# v15.net
KiCad netlist of a schematic drawn in EAGLE
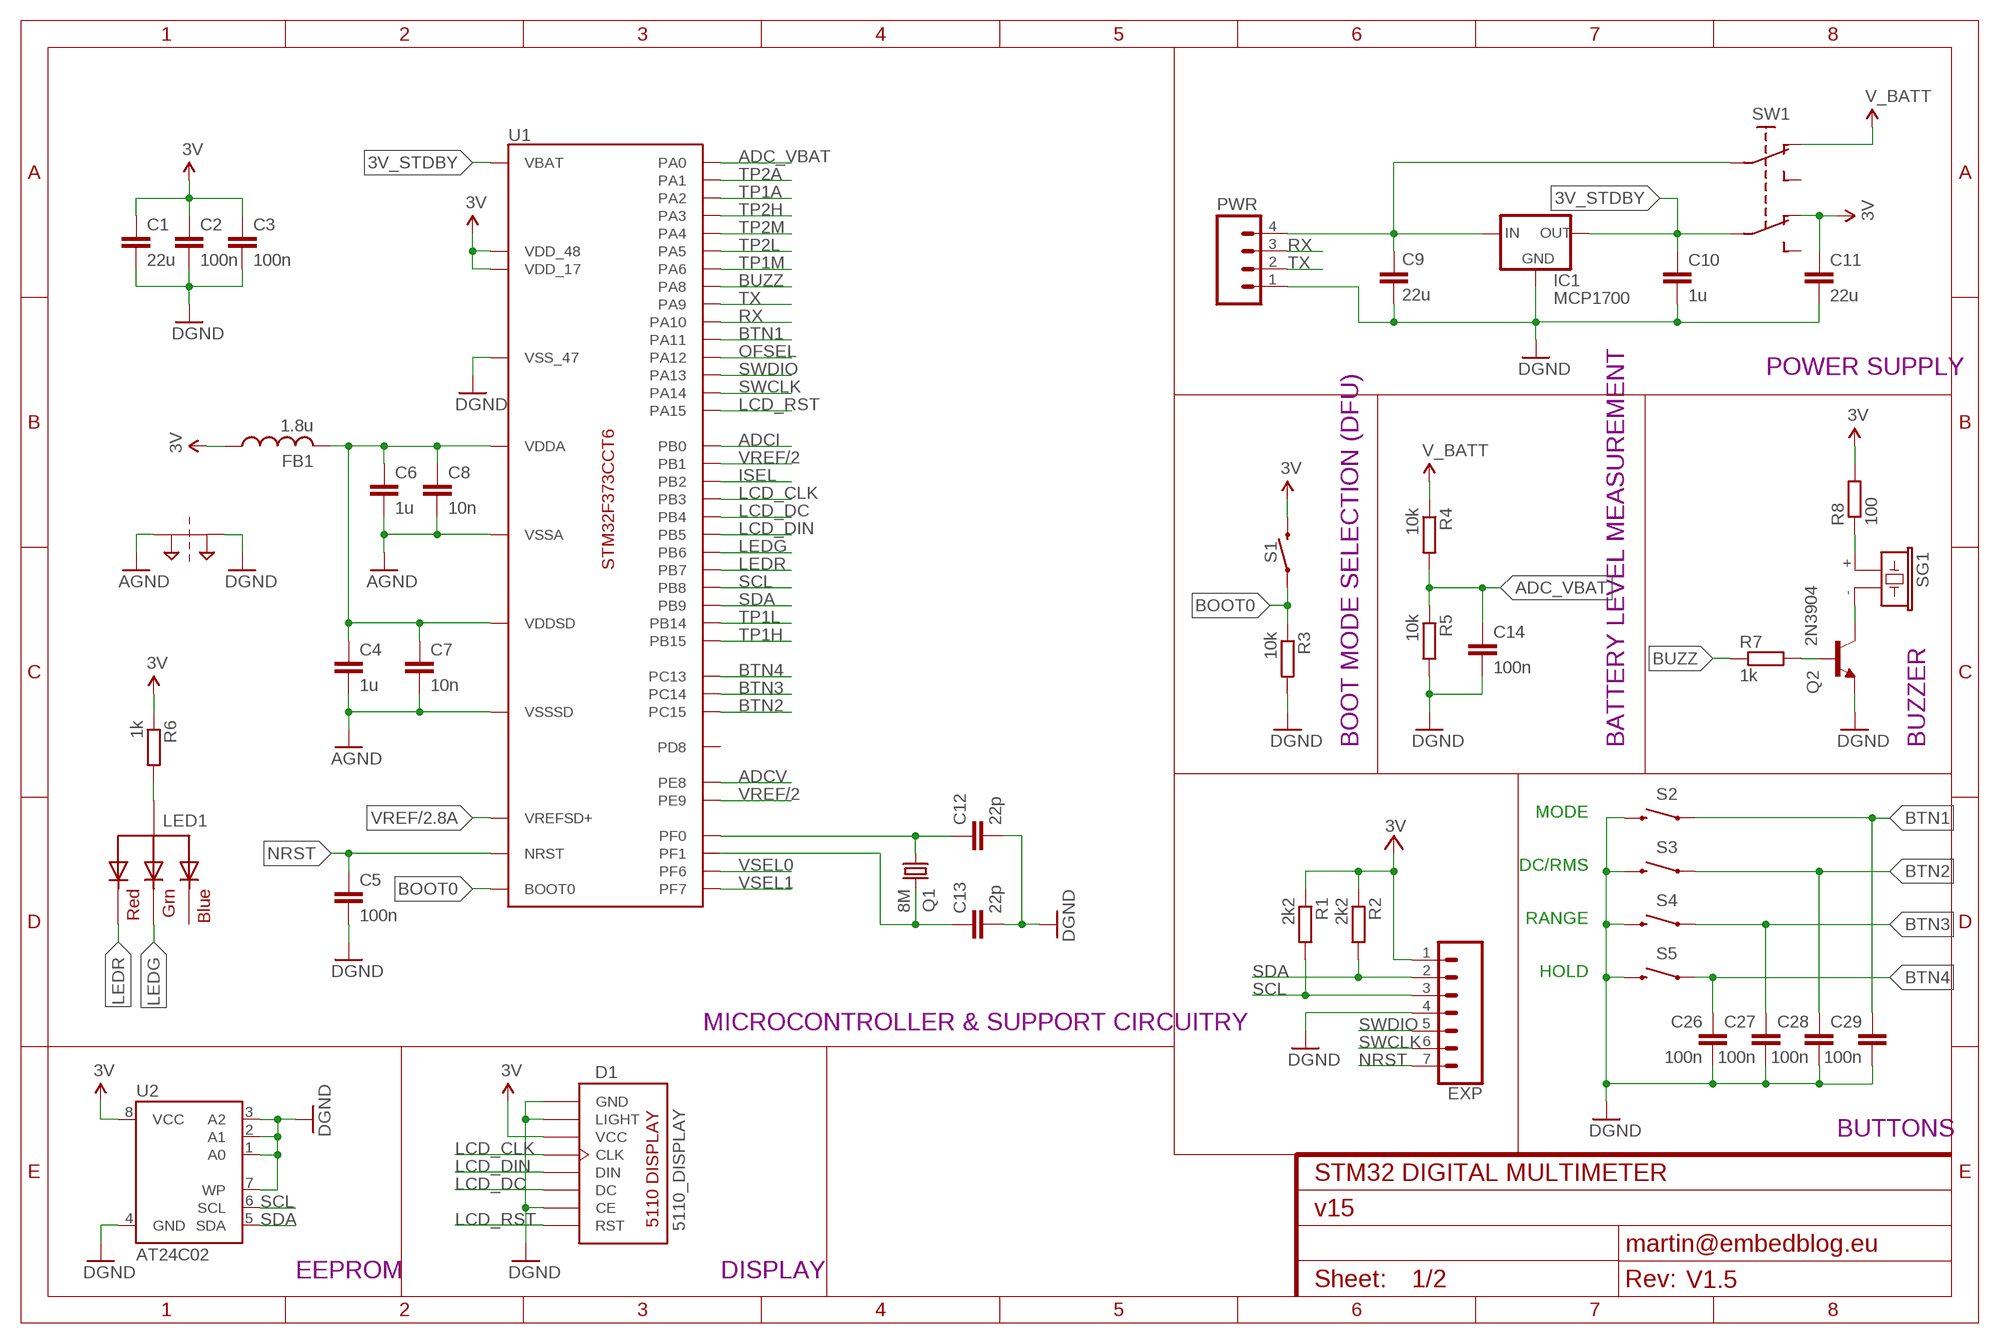
[diagram p0: schematic, sheet 1]
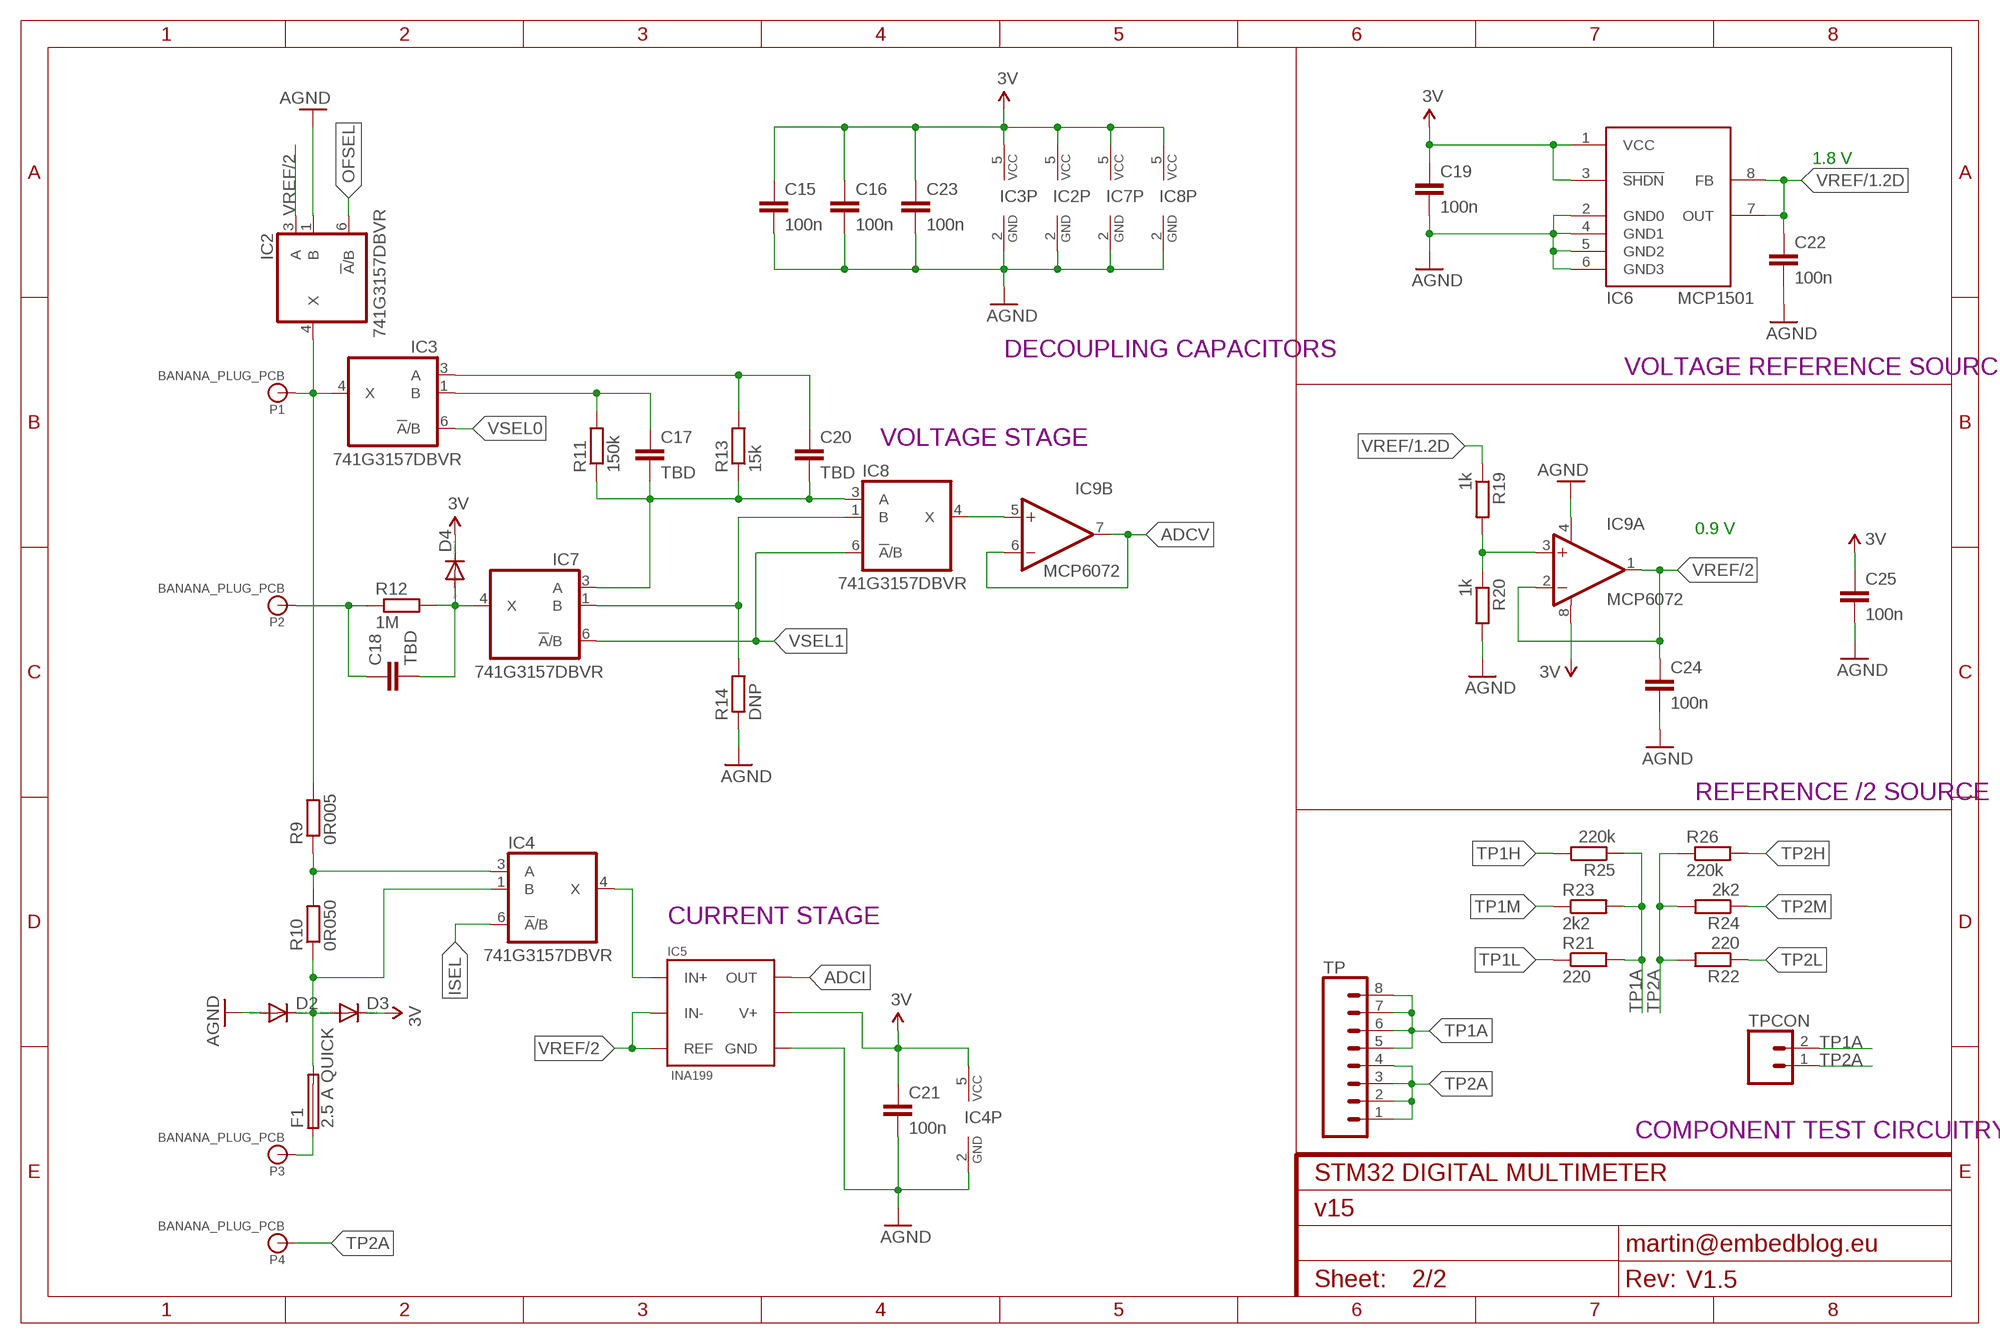
[diagram p1: schematic, sheet 2]

(export (version "E")
  (design (tool "Eeschema 10.0.6"))
  (components
    (comp (ref "C1")
      (value "22u")
      (footprint "eagle-import:C1206")
      (libsource (lib "eagle-import") (part "C-EUC1206"))
    )
    (comp (ref "C2")
      (value "100n")
      (footprint "eagle-import:C1206")
      (libsource (lib "eagle-import") (part "C-EUC1206"))
    )
    (comp (ref "C3")
      (value "100n")
      (footprint "eagle-import:C1206")
      (libsource (lib "eagle-import") (part "C-EUC1206"))
    )
    (comp (ref "C4")
      (value "1u")
      (footprint "eagle-import:C1206")
      (libsource (lib "eagle-import") (part "C-EUC1206"))
    )
    (comp (ref "C5")
      (value "100n")
      (footprint "eagle-import:C1206")
      (libsource (lib "eagle-import") (part "C-EUC1206"))
    )
    (comp (ref "C6")
      (value "1u")
      (footprint "eagle-import:C1206")
      (libsource (lib "eagle-import") (part "C-EUC1206"))
    )
    (comp (ref "C7")
      (value "10n")
      (footprint "eagle-import:C1206")
      (libsource (lib "eagle-import") (part "C-EUC1206"))
    )
    (comp (ref "C8")
      (value "10n")
      (footprint "eagle-import:C1206")
      (libsource (lib "eagle-import") (part "C-EUC1206"))
    )
    (comp (ref "C9")
      (value "22u")
      (footprint "eagle-import:C1206")
      (libsource (lib "eagle-import") (part "C-EUC1206"))
    )
    (comp (ref "C10")
      (value "1u")
      (footprint "eagle-import:C1206")
      (libsource (lib "eagle-import") (part "C-EUC1206"))
    )
    (comp (ref "C11")
      (value "22u")
      (footprint "eagle-import:C1206")
      (libsource (lib "eagle-import") (part "C-EUC1206"))
    )
    (comp (ref "C12")
      (value "22p")
      (footprint "eagle-import:C1206")
      (libsource (lib "eagle-import") (part "C-EUC1206"))
    )
    (comp (ref "C13")
      (value "22p")
      (footprint "eagle-import:C1206")
      (libsource (lib "eagle-import") (part "C-EUC1206"))
    )
    (comp (ref "C14")
      (value "100n")
      (footprint "eagle-import:C1206")
      (libsource (lib "eagle-import") (part "C-EUC1206"))
    )
    (comp (ref "C26")
      (value "100n")
      (footprint "eagle-import:C1206")
      (libsource (lib "eagle-import") (part "C-EUC1206"))
    )
    (comp (ref "C27")
      (value "100n")
      (footprint "eagle-import:C1206")
      (libsource (lib "eagle-import") (part "C-EUC1206"))
    )
    (comp (ref "C28")
      (value "100n")
      (footprint "eagle-import:C1206")
      (libsource (lib "eagle-import") (part "C-EUC1206"))
    )
    (comp (ref "C29")
      (value "100n")
      (footprint "eagle-import:C1206")
      (libsource (lib "eagle-import") (part "C-EUC1206"))
    )
    (comp (ref "D1")
      (value "5110_DISPLAY")
      (footprint "eagle-import:5110_LAYOUT")
      (libsource (lib "eagle-import") (part "5110_DISPLAY"))
    )
    (comp (ref "EXP")
      (value "CONN_07")
      (footprint "eagle-import:1X07")
      (libsource (lib "eagle-import") (part "CONN_07"))
    )
    (comp (ref "FB1")
      (value "1.8u")
      (footprint "eagle-import:1206")
      (libsource (lib "eagle-import") (part "FERRITE-BEADC"))
    )
    (comp (ref "IC1")
      (value "MCP1700")
      (footprint "eagle-import:SOT23")
      (libsource (lib "eagle-import") (part "XC63FPM"))
    )
    (comp (ref "LED1")
      (value "RGBLED_CA-5MM")
      (footprint "eagle-import:LED5MMRGB")
      (libsource (lib "eagle-import") (part "RGBLED_CA-5MM"))
    )
    (comp (ref "PT1")
      (value "2PT_GND_TIE")
      (footprint "eagle-import:2PT_GND_TIE")
      (libsource (lib "eagle-import") (part "2PT_GND_TIE"))
    )
    (comp (ref "PWR")
      (value "M04PTH")
      (footprint "eagle-import:1X04@1")
      (libsource (lib "eagle-import") (part "M04PTH"))
    )
    (comp (ref "Q1")
      (value "8M")
      (footprint "eagle-import:HC49U-V")
      (libsource (lib "eagle-import") (part "CRYSTALHC49U-V"))
    )
    (comp (ref "Q2")
      (value "2N3904")
      (footprint "eagle-import:SOT23")
      (libsource (lib "eagle-import") (part "2N3904-MMBT"))
    )
    (comp (ref "R1")
      (value "2k2")
      (footprint "eagle-import:R1206")
      (libsource (lib "eagle-import") (part "R-EU_R1206"))
    )
    (comp (ref "R2")
      (value "2k2")
      (footprint "eagle-import:R1206")
      (libsource (lib "eagle-import") (part "R-EU_R1206"))
    )
    (comp (ref "R3")
      (value "10k")
      (footprint "eagle-import:R1206")
      (libsource (lib "eagle-import") (part "R-EU_R1206"))
    )
    (comp (ref "R4")
      (value "10k")
      (footprint "eagle-import:R1206")
      (libsource (lib "eagle-import") (part "R-EU_R1206"))
    )
    (comp (ref "R5")
      (value "10k")
      (footprint "eagle-import:R1206")
      (libsource (lib "eagle-import") (part "R-EU_R1206"))
    )
    (comp (ref "R6")
      (value "1k")
      (footprint "eagle-import:R1206")
      (libsource (lib "eagle-import") (part "R-EU_R1206"))
    )
    (comp (ref "R7")
      (value "1k")
      (footprint "eagle-import:R1206")
      (libsource (lib "eagle-import") (part "R-EU_R1206"))
    )
    (comp (ref "R8")
      (value "100")
      (footprint "eagle-import:R1206")
      (libsource (lib "eagle-import") (part "R-EU_R1206"))
    )
    (comp (ref "S1")
      (value "MOMENTARY-SWITCH-SPST-PTH-6.0MM")
      (footprint "eagle-import:TACTILE_SWITCH_PTH_6.0MM")
      (libsource (lib "eagle-import") (part "MOMENTARY-SWITCH-SPST-PTH-6.0MM"))
    )
    (comp (ref "S2")
      (value "MOMENTARY-SWITCH-SPST-SMD-12MM")
      (footprint "eagle-import:TACTILE_SWITCH_SMD_12MM")
      (libsource (lib "eagle-import") (part "MOMENTARY-SWITCH-SPST-SMD-12MM"))
    )
    (comp (ref "S3")
      (value "MOMENTARY-SWITCH-SPST-SMD-12MM")
      (footprint "eagle-import:TACTILE_SWITCH_SMD_12MM")
      (libsource (lib "eagle-import") (part "MOMENTARY-SWITCH-SPST-SMD-12MM"))
    )
    (comp (ref "S4")
      (value "MOMENTARY-SWITCH-SPST-SMD-12MM")
      (footprint "eagle-import:TACTILE_SWITCH_SMD_12MM")
      (libsource (lib "eagle-import") (part "MOMENTARY-SWITCH-SPST-SMD-12MM"))
    )
    (comp (ref "S5")
      (value "MOMENTARY-SWITCH-SPST-SMD-12MM")
      (footprint "eagle-import:TACTILE_SWITCH_SMD_12MM")
      (libsource (lib "eagle-import") (part "MOMENTARY-SWITCH-SPST-SMD-12MM"))
    )
    (comp (ref "SG1")
      (value "F/CM12P")
      (footprint "eagle-import:F_CM12P")
      (libsource (lib "eagle-import") (part "F/CM12P"))
    )
    (comp (ref "SW1")
      (value "DPDT_SWITCH_SMALL")
      (footprint "eagle-import:DPDT_SMALL")
      (libsource (lib "eagle-import") (part "DPDT_SWITCH_SMALL"))
    )
    (comp (ref "U1")
      (value "STM32F373CCT6")
      (footprint "eagle-import:LQFP-48")
      (libsource (lib "eagle-import") (part "STM32F373CCT6"))
    )
    (comp (ref "U2")
      (value "AT24C02")
      (footprint "eagle-import:SOIC8")
      (libsource (lib "eagle-import") (part "24LCXX"))
    )
    (comp (ref "C15")
      (value "100n")
      (footprint "eagle-import:1206")
      (libsource (lib "eagle-import") (part "CAP1206"))
    )
    (comp (ref "C16")
      (value "100n")
      (footprint "eagle-import:1206")
      (libsource (lib "eagle-import") (part "CAP1206"))
    )
    (comp (ref "C17")
      (value "TBD")
      (footprint "eagle-import:1206")
      (libsource (lib "eagle-import") (part "CAP1206"))
    )
    (comp (ref "C18")
      (value "TBD")
      (footprint "eagle-import:1206")
      (libsource (lib "eagle-import") (part "CAP1206"))
    )
    (comp (ref "C19")
      (value "100n")
      (footprint "eagle-import:C1206")
      (libsource (lib "eagle-import") (part "C-EUC1206"))
    )
    (comp (ref "C20")
      (value "TBD")
      (footprint "eagle-import:1206")
      (libsource (lib "eagle-import") (part "CAP1206"))
    )
    (comp (ref "C21")
      (value "100n")
      (footprint "eagle-import:1206")
      (libsource (lib "eagle-import") (part "CAP1206"))
    )
    (comp (ref "C22")
      (value "100n")
      (footprint "eagle-import:C1206")
      (libsource (lib "eagle-import") (part "C-EUC1206"))
    )
    (comp (ref "C23")
      (value "100n")
      (footprint "eagle-import:1206")
      (libsource (lib "eagle-import") (part "CAP1206"))
    )
    (comp (ref "C24")
      (value "100n")
      (footprint "eagle-import:C1206")
      (libsource (lib "eagle-import") (part "C-EUC1206"))
    )
    (comp (ref "C25")
      (value "100n")
      (footprint "eagle-import:C1206")
      (libsource (lib "eagle-import") (part "C-EUC1206"))
    )
    (comp (ref "D2")
      (value "DIODE-MINIMELF")
      (footprint "eagle-import:MINIMELF")
      (libsource (lib "eagle-import") (part "DIODE-MINIMELF"))
    )
    (comp (ref "D3")
      (value "DIODE-MINIMELF")
      (footprint "eagle-import:MINIMELF")
      (libsource (lib "eagle-import") (part "DIODE-MINIMELF"))
    )
    (comp (ref "D4")
      (value "DIODE-MINIMELF")
      (footprint "eagle-import:MINIMELF")
      (libsource (lib "eagle-import") (part "DIODE-MINIMELF"))
    )
    (comp (ref "F1")
      (value "2.5 A QUICK")
      (footprint "eagle-import:SHK20L")
      (libsource (lib "eagle-import") (part "FUSESHK20L"))
    )
    (comp (ref "IC2")
      (value "741G3157DBVR")
      (footprint "eagle-import:DBV_R-PDSO-G6")
      (libsource (lib "eagle-import") (part "741G3157DBVR"))
    )
    (comp (ref "IC3")
      (value "741G3157DBVR")
      (footprint "eagle-import:DBV_R-PDSO-G6")
      (libsource (lib "eagle-import") (part "741G3157DBVR"))
    )
    (comp (ref "IC4")
      (value "741G3157DBVR")
      (footprint "eagle-import:DBV_R-PDSO-G6")
      (libsource (lib "eagle-import") (part "741G3157DBVR"))
    )
    (comp (ref "IC5")
      (value "INA199")
      (footprint "eagle-import:SC70-6")
      (libsource (lib "eagle-import") (part "INA199"))
    )
    (comp (ref "IC6")
      (value "MCP1501")
      (footprint "eagle-import:SO08")
      (libsource (lib "eagle-import") (part "MCP1501"))
    )
    (comp (ref "IC7")
      (value "741G3157DBVR")
      (footprint "eagle-import:DBV_R-PDSO-G6")
      (libsource (lib "eagle-import") (part "741G3157DBVR"))
    )
    (comp (ref "IC8")
      (value "741G3157DBVR")
      (footprint "eagle-import:DBV_R-PDSO-G6")
      (libsource (lib "eagle-import") (part "741G3157DBVR"))
    )
    (comp (ref "IC9")
      (value "MCP6072")
      (footprint "eagle-import:SO08")
      (libsource (lib "eagle-import") (part "OPAMP-DUALU"))
    )
    (comp (ref "P1")
      (value "BANANA_PLUG_PCB")
      (footprint "eagle-import:BANANA_6MMHOLE")
      (libsource (lib "eagle-import") (part "BANANA_PLUG_PCB"))
    )
    (comp (ref "P2")
      (value "BANANA_PLUG_PCB")
      (footprint "eagle-import:BANANA_6MMHOLE")
      (libsource (lib "eagle-import") (part "BANANA_PLUG_PCB"))
    )
    (comp (ref "P3")
      (value "BANANA_PLUG_PCB")
      (footprint "eagle-import:BANANA_6MMHOLE")
      (libsource (lib "eagle-import") (part "BANANA_PLUG_PCB"))
    )
    (comp (ref "P4")
      (value "BANANA_PLUG_PCB")
      (footprint "eagle-import:BANANA_6MMHOLE")
      (libsource (lib "eagle-import") (part "BANANA_PLUG_PCB"))
    )
    (comp (ref "R9")
      (value "0R005")
      (footprint "eagle-import:R1206")
      (libsource (lib "eagle-import") (part "R-EU_R1206"))
    )
    (comp (ref "R10")
      (value "0R050")
      (footprint "eagle-import:R1206")
      (libsource (lib "eagle-import") (part "R-EU_R1206"))
    )
    (comp (ref "R11")
      (value "150k")
      (footprint "eagle-import:R1206")
      (libsource (lib "eagle-import") (part "R-EU_R1206"))
    )
    (comp (ref "R12")
      (value "1M")
      (footprint "eagle-import:R1206")
      (libsource (lib "eagle-import") (part "R-EU_R1206"))
    )
    (comp (ref "R13")
      (value "15k")
      (footprint "eagle-import:R1206")
      (libsource (lib "eagle-import") (part "R-EU_R1206"))
    )
    (comp (ref "R14")
      (value "DNP")
      (footprint "eagle-import:R1206")
      (libsource (lib "eagle-import") (part "R-EU_R1206"))
    )
    (comp (ref "R19")
      (value "1k")
      (footprint "eagle-import:R1206")
      (libsource (lib "eagle-import") (part "R-EU_R1206"))
    )
    (comp (ref "R20")
      (value "1k")
      (footprint "eagle-import:R1206")
      (libsource (lib "eagle-import") (part "R-EU_R1206"))
    )
    (comp (ref "R21")
      (value "220")
      (footprint "eagle-import:R1206")
      (libsource (lib "eagle-import") (part "R-EU_R1206"))
    )
    (comp (ref "R22")
      (value "220")
      (footprint "eagle-import:R1206")
      (libsource (lib "eagle-import") (part "R-EU_R1206"))
    )
    (comp (ref "R23")
      (value "2k2")
      (footprint "eagle-import:R1206")
      (libsource (lib "eagle-import") (part "R-EU_R1206"))
    )
    (comp (ref "R24")
      (value "2k2")
      (footprint "eagle-import:R1206")
      (libsource (lib "eagle-import") (part "R-EU_R1206"))
    )
    (comp (ref "R25")
      (value "220k")
      (footprint "eagle-import:R1206")
      (libsource (lib "eagle-import") (part "R-EU_R1206"))
    )
    (comp (ref "R26")
      (value "220k")
      (footprint "eagle-import:R1206")
      (libsource (lib "eagle-import") (part "R-EU_R1206"))
    )
    (comp (ref "TP")
      (value "CONN_08SMD-STRAIGHT-FEMALE")
      (footprint "eagle-import:1X08_SMD")
      (libsource (lib "eagle-import") (part "CONN_08SMD-STRAIGHT-FEMALE"))
    )
    (comp (ref "TPCON")
      (value "CONN_02")
      (footprint "eagle-import:1X02")
      (libsource (lib "eagle-import") (part "CONN_02"))
    )
  )
  (nets
    (net (code "1") (name "3V") (class "Default")
      (node (ref "C1") (pin "1") (pinfunction "1_1") (pintype "passive"))
      (node (ref "C11") (pin "1") (pinfunction "1_1") (pintype "passive"))
      (node (ref "C15") (pin "1") (pinfunction "1_1") (pintype "passive"))
      (node (ref "C16") (pin "1") (pinfunction "1_1") (pintype "passive"))
      (node (ref "C19") (pin "1") (pinfunction "1_1") (pintype "passive"))
      (node (ref "C2") (pin "1") (pinfunction "1_1") (pintype "passive"))
      (node (ref "C21") (pin "1") (pinfunction "1_1") (pintype "passive"))
      (node (ref "C23") (pin "1") (pinfunction "1_1") (pintype "passive"))
      (node (ref "C25") (pin "1") (pinfunction "1_1") (pintype "passive"))
      (node (ref "C3") (pin "1") (pinfunction "1_1") (pintype "passive"))
      (node (ref "D1") (pin "VCC") (pinfunction "VCC_VCC") (pintype "bidirectional"))
      (node (ref "D3") (pin "C") (pinfunction "C_C") (pintype "passive"))
      (node (ref "D4") (pin "C") (pinfunction "C_C") (pintype "passive"))
      (node (ref "EXP") (pin "1") (pinfunction "1_1") (pintype "passive"))
      (node (ref "FB1") (pin "1") (pinfunction "1_1") (pintype "passive"))
      (node (ref "IC2") (pin "5") (pinfunction "VCC_5") (pintype "power_in"))
      (node (ref "IC3") (pin "5") (pinfunction "VCC_5") (pintype "power_in"))
      (node (ref "IC4") (pin "5") (pinfunction "VCC_5") (pintype "power_in"))
      (node (ref "IC5") (pin "3") (pinfunction "V+_3") (pintype "bidirectional"))
      (node (ref "IC6") (pin "1") (pinfunction "VCC_1") (pintype "bidirectional"))
      (node (ref "IC6") (pin "3") (pinfunction "~{SHDN}_3") (pintype "bidirectional"))
      (node (ref "IC7") (pin "5") (pinfunction "VCC_5") (pintype "power_in"))
      (node (ref "IC8") (pin "5") (pinfunction "VCC_5") (pintype "power_in"))
      (node (ref "IC9") (pin "8") (pinfunction "V+_8") (pintype "power_in"))
      (node (ref "R1") (pin "1") (pinfunction "1_1") (pintype "passive"))
      (node (ref "R2") (pin "1") (pinfunction "1_1") (pintype "passive"))
      (node (ref "R6") (pin "1") (pinfunction "1_1") (pintype "passive"))
      (node (ref "R8") (pin "2") (pinfunction "2_2") (pintype "passive"))
      (node (ref "S1") (pin "3") (pinfunction "2_3") (pintype "passive"))
      (node (ref "SW1") (pin "P$6") (pinfunction "NC2_P$6") (pintype "passive"))
      (node (ref "U1") (pin "17") (pinfunction "VDD_17_17") (pintype "bidirectional"))
      (node (ref "U1") (pin "48") (pinfunction "VDD_48_48") (pintype "bidirectional"))
      (node (ref "U2") (pin "8") (pinfunction "VCC_8") (pintype "power_in"))
    )
    (net (code "2") (name "3V_STDBY") (class "Default")
      (node (ref "C10") (pin "1") (pinfunction "1_1") (pintype "passive"))
      (node (ref "IC1") (pin "2") (pinfunction "OUT_2") (pintype "passive"))
      (node (ref "SW1") (pin "P$5") (pinfunction "I2_P$5") (pintype "passive"))
      (node (ref "U1") (pin "1") (pinfunction "VBAT_1") (pintype "bidirectional"))
    )
    (net (code "3") (name "ADCI") (class "Default")
      (node (ref "IC5") (pin "6") (pinfunction "OUT_6") (pintype "bidirectional"))
      (node (ref "U1") (pin "18") (pinfunction "PB0_18") (pintype "bidirectional"))
    )
    (net (code "4") (name "ADCV") (class "Default")
      (node (ref "IC9") (pin "6") (pinfunction "-IN_6") (pintype "input"))
      (node (ref "IC9") (pin "7") (pinfunction "OUT_7") (pintype "output"))
      (node (ref "U1") (pin "21") (pinfunction "PE8_21") (pintype "bidirectional"))
    )
    (net (code "5") (name "ADC_VBAT") (class "Default")
      (node (ref "C14") (pin "1") (pinfunction "1_1") (pintype "passive"))
      (node (ref "R4") (pin "2") (pinfunction "2_2") (pintype "passive"))
      (node (ref "R5") (pin "1") (pinfunction "1_1") (pintype "passive"))
      (node (ref "U1") (pin "10") (pinfunction "PA0_10") (pintype "bidirectional"))
    )
    (net (code "6") (name "AGND") (class "Default")
      (node (ref "C15") (pin "2") (pinfunction "2_2") (pintype "passive"))
      (node (ref "C16") (pin "2") (pinfunction "2_2") (pintype "passive"))
      (node (ref "C19") (pin "2") (pinfunction "2_2") (pintype "passive"))
      (node (ref "C21") (pin "2") (pinfunction "2_2") (pintype "passive"))
      (node (ref "C22") (pin "2") (pinfunction "2_2") (pintype "passive"))
      (node (ref "C23") (pin "2") (pinfunction "2_2") (pintype "passive"))
      (node (ref "C24") (pin "2") (pinfunction "2_2") (pintype "passive"))
      (node (ref "C25") (pin "2") (pinfunction "2_2") (pintype "passive"))
      (node (ref "C4") (pin "2") (pinfunction "2_2") (pintype "passive"))
      (node (ref "C6") (pin "2") (pinfunction "2_2") (pintype "passive"))
      (node (ref "C7") (pin "2") (pinfunction "2_2") (pintype "passive"))
      (node (ref "C8") (pin "2") (pinfunction "2_2") (pintype "passive"))
      (node (ref "D2") (pin "A") (pinfunction "A_A") (pintype "passive"))
      (node (ref "IC2") (pin "1") (pinfunction "B_1") (pintype "bidirectional"))
      (node (ref "IC2") (pin "2") (pinfunction "GND_2") (pintype "power_in"))
      (node (ref "IC3") (pin "2") (pinfunction "GND_2") (pintype "power_in"))
      (node (ref "IC4") (pin "2") (pinfunction "GND_2") (pintype "power_in"))
      (node (ref "IC5") (pin "2") (pinfunction "GND_2") (pintype "bidirectional"))
      (node (ref "IC6") (pin "2") (pinfunction "GND0_2") (pintype "bidirectional"))
      (node (ref "IC6") (pin "4") (pinfunction "GND1_4") (pintype "bidirectional"))
      (node (ref "IC6") (pin "5") (pinfunction "GND2_5") (pintype "bidirectional"))
      (node (ref "IC6") (pin "6") (pinfunction "GND3_6") (pintype "bidirectional"))
      (node (ref "IC7") (pin "2") (pinfunction "GND_2") (pintype "power_in"))
      (node (ref "IC8") (pin "2") (pinfunction "GND_2") (pintype "power_in"))
      (node (ref "IC9") (pin "4") (pinfunction "V-_4") (pintype "power_in"))
      (node (ref "PT1") (pin "P$1") (pinfunction "P$1_P$1") (pintype "bidirectional"))
      (node (ref "R14") (pin "1") (pinfunction "1_1") (pintype "passive"))
      (node (ref "R20") (pin "2") (pinfunction "2_2") (pintype "passive"))
      (node (ref "U1") (pin "23") (pinfunction "VSSSD_23") (pintype "bidirectional"))
      (node (ref "U1") (pin "8") (pinfunction "VSSA_8") (pintype "bidirectional"))
    )
    (net (code "7") (name "BOOT0") (class "Default")
      (node (ref "R3") (pin "1") (pinfunction "1_1") (pintype "passive"))
      (node (ref "S1") (pin "1") (pinfunction "1_1") (pintype "passive"))
      (node (ref "U1") (pin "44") (pinfunction "BOOT0_44") (pintype "bidirectional"))
    )
    (net (code "8") (name "BTN1") (class "Default")
      (node (ref "C29") (pin "1") (pinfunction "1_1") (pintype "passive"))
      (node (ref "S2") (pin "1") (pinfunction "1_1") (pintype "passive"))
      (node (ref "U1") (pin "32") (pinfunction "PA11_32") (pintype "bidirectional"))
    )
    (net (code "9") (name "BTN2") (class "Default")
      (node (ref "C28") (pin "1") (pinfunction "1_1") (pintype "passive"))
      (node (ref "S3") (pin "1") (pinfunction "1_1") (pintype "passive"))
      (node (ref "U1") (pin "4") (pinfunction "PC15_4") (pintype "bidirectional"))
    )
    (net (code "10") (name "BTN3") (class "Default")
      (node (ref "C27") (pin "1") (pinfunction "1_1") (pintype "passive"))
      (node (ref "S4") (pin "1") (pinfunction "1_1") (pintype "passive"))
      (node (ref "U1") (pin "3") (pinfunction "PC14_3") (pintype "bidirectional"))
    )
    (net (code "11") (name "BTN4") (class "Default")
      (node (ref "C26") (pin "1") (pinfunction "1_1") (pintype "passive"))
      (node (ref "S5") (pin "1") (pinfunction "1_1") (pintype "passive"))
      (node (ref "U1") (pin "2") (pinfunction "PC13_2") (pintype "bidirectional"))
    )
    (net (code "12") (name "BUZZ") (class "Default")
      (node (ref "R7") (pin "1") (pinfunction "1_1") (pintype "passive"))
      (node (ref "U1") (pin "29") (pinfunction "PA8_29") (pintype "bidirectional"))
    )
    (net (code "13") (name "GND") (class "Default")
      (node (ref "C1") (pin "2") (pinfunction "2_2") (pintype "passive"))
      (node (ref "C10") (pin "2") (pinfunction "2_2") (pintype "passive"))
      (node (ref "C11") (pin "2") (pinfunction "2_2") (pintype "passive"))
      (node (ref "C12") (pin "2") (pinfunction "2_2") (pintype "passive"))
      (node (ref "C13") (pin "2") (pinfunction "2_2") (pintype "passive"))
      (node (ref "C14") (pin "2") (pinfunction "2_2") (pintype "passive"))
      (node (ref "C2") (pin "2") (pinfunction "2_2") (pintype "passive"))
      (node (ref "C26") (pin "2") (pinfunction "2_2") (pintype "passive"))
      (node (ref "C27") (pin "2") (pinfunction "2_2") (pintype "passive"))
      (node (ref "C28") (pin "2") (pinfunction "2_2") (pintype "passive"))
      (node (ref "C29") (pin "2") (pinfunction "2_2") (pintype "passive"))
      (node (ref "C3") (pin "2") (pinfunction "2_2") (pintype "passive"))
      (node (ref "C5") (pin "2") (pinfunction "2_2") (pintype "passive"))
      (node (ref "C9") (pin "2") (pinfunction "2_2") (pintype "passive"))
      (node (ref "D1") (pin "CE") (pinfunction "CE_CE") (pintype "bidirectional"))
      (node (ref "D1") (pin "GND") (pinfunction "GND_GND") (pintype "bidirectional"))
      (node (ref "D1") (pin "LIGHT") (pinfunction "LIGHT_LIGHT") (pintype "bidirectional"))
      (node (ref "EXP") (pin "4") (pinfunction "4_4") (pintype "passive"))
      (node (ref "IC1") (pin "1") (pinfunction "GND_1") (pintype "input"))
      (node (ref "PT1") (pin "P$2") (pinfunction "P$2_P$2") (pintype "bidirectional"))
      (node (ref "PWR") (pin "1") (pinfunction "1_1") (pintype "passive"))
      (node (ref "Q2") (pin "2") (pinfunction "E_2") (pintype "passive"))
      (node (ref "R3") (pin "2") (pinfunction "2_2") (pintype "passive"))
      (node (ref "R5") (pin "2") (pinfunction "2_2") (pintype "passive"))
      (node (ref "S2") (pin "3") (pinfunction "2_3") (pintype "passive"))
      (node (ref "S3") (pin "3") (pinfunction "2_3") (pintype "passive"))
      (node (ref "S4") (pin "3") (pinfunction "2_3") (pintype "passive"))
      (node (ref "S5") (pin "3") (pinfunction "2_3") (pintype "passive"))
      (node (ref "U1") (pin "47") (pinfunction "VSS_47_47") (pintype "bidirectional"))
      (node (ref "U2") (pin "1") (pinfunction "A0_1") (pintype "input"))
      (node (ref "U2") (pin "2") (pinfunction "A1_2") (pintype "input"))
      (node (ref "U2") (pin "3") (pinfunction "A2_3") (pintype "input"))
      (node (ref "U2") (pin "4") (pinfunction "GND_4") (pintype "power_in"))
      (node (ref "U2") (pin "7") (pinfunction "WP_7") (pintype "input"))
    )
    (net (code "14") (name "ISEL") (class "Default")
      (node (ref "IC4") (pin "6") (pinfunction "~{A}/B_6") (pintype "input"))
      (node (ref "U1") (pin "20") (pinfunction "PB2_20") (pintype "bidirectional"))
    )
    (net (code "15") (name "LCD_CLK") (class "Default")
      (node (ref "D1") (pin "CLK") (pinfunction "CLK_CLK") (pintype "bidirectional"))
      (node (ref "U1") (pin "39") (pinfunction "PB3_39") (pintype "bidirectional"))
    )
    (net (code "16") (name "LCD_DC") (class "Default")
      (node (ref "D1") (pin "DC") (pinfunction "DC_DC") (pintype "bidirectional"))
      (node (ref "U1") (pin "40") (pinfunction "PB4_40") (pintype "bidirectional"))
    )
    (net (code "17") (name "LCD_DIN") (class "Default")
      (node (ref "D1") (pin "DIN") (pinfunction "DIN_DIN") (pintype "bidirectional"))
      (node (ref "U1") (pin "41") (pinfunction "PB5_41") (pintype "bidirectional"))
    )
    (net (code "18") (name "LCD_RST") (class "Default")
      (node (ref "D1") (pin "RST") (pinfunction "RST_RST") (pintype "bidirectional"))
      (node (ref "U1") (pin "38") (pinfunction "PA15_38") (pintype "bidirectional"))
    )
    (net (code "19") (name "LEDG") (class "Default")
      (node (ref "LED1") (pin "3") (pinfunction "GREEN_3") (pintype "bidirectional"))
      (node (ref "U1") (pin "42") (pinfunction "PB6_42") (pintype "bidirectional"))
    )
    (net (code "20") (name "LEDR") (class "Default")
      (node (ref "LED1") (pin "1") (pinfunction "RED_1") (pintype "bidirectional"))
      (node (ref "U1") (pin "43") (pinfunction "PB7_43") (pintype "bidirectional"))
    )
    (net (code "21") (name "NRST") (class "Default")
      (node (ref "C5") (pin "1") (pinfunction "1_1") (pintype "passive"))
      (node (ref "EXP") (pin "7") (pinfunction "7_7") (pintype "passive"))
      (node (ref "U1") (pin "7") (pinfunction "NRST_7") (pintype "bidirectional"))
    )
    (net (code "22") (name "Net-(F1-1)") (class "Default")
      (node (ref "F1") (pin "1A") (pinfunction "1_1A") (pintype "passive"))
      (node (ref "P3") (pin "P$1") (pinfunction "1_P$1") (pintype "passive"))
    )
    (net (code "23") (name "Net-(F1-2)") (class "Default")
      (node (ref "D2") (pin "C") (pinfunction "C_C") (pintype "passive"))
      (node (ref "D3") (pin "A") (pinfunction "A_A") (pintype "passive"))
      (node (ref "F1") (pin "2A") (pinfunction "2_2A") (pintype "passive"))
      (node (ref "IC4") (pin "1") (pinfunction "B_1") (pintype "bidirectional"))
      (node (ref "R10") (pin "1") (pinfunction "1_1") (pintype "passive"))
    )
    (net (code "24") (name "Net-(IC1-IN)") (class "Default")
      (node (ref "C9") (pin "1") (pinfunction "1_1") (pintype "passive"))
      (node (ref "IC1") (pin "3") (pinfunction "IN_3") (pintype "input"))
      (node (ref "PWR") (pin "4") (pinfunction "4_4") (pintype "passive"))
      (node (ref "SW1") (pin "P$2") (pinfunction "I1_P$2") (pintype "passive"))
    )
    (net (code "25") (name "Net-(IC2A-X)") (class "Default")
      (node (ref "IC2") (pin "4") (pinfunction "X_4") (pintype "bidirectional"))
      (node (ref "IC3") (pin "4") (pinfunction "X_4") (pintype "bidirectional"))
      (node (ref "P1") (pin "P$1") (pinfunction "1_P$1") (pintype "passive"))
      (node (ref "R9") (pin "2") (pinfunction "2_2") (pintype "passive"))
    )
    (net (code "26") (name "Net-(IC3A-A)") (class "Default")
      (node (ref "C20") (pin "1") (pinfunction "1_1") (pintype "passive"))
      (node (ref "IC3") (pin "3") (pinfunction "A_3") (pintype "bidirectional"))
      (node (ref "R13") (pin "2") (pinfunction "2_2") (pintype "passive"))
    )
    (net (code "27") (name "Net-(IC3A-B)") (class "Default")
      (node (ref "C17") (pin "1") (pinfunction "1_1") (pintype "passive"))
      (node (ref "IC3") (pin "1") (pinfunction "B_1") (pintype "bidirectional"))
      (node (ref "R11") (pin "2") (pinfunction "2_2") (pintype "passive"))
    )
    (net (code "28") (name "Net-(IC4A-A)") (class "Default")
      (node (ref "IC4") (pin "3") (pinfunction "A_3") (pintype "bidirectional"))
      (node (ref "R10") (pin "2") (pinfunction "2_2") (pintype "passive"))
      (node (ref "R9") (pin "1") (pinfunction "1_1") (pintype "passive"))
    )
    (net (code "29") (name "Net-(IC4A-X)") (class "Default")
      (node (ref "IC4") (pin "4") (pinfunction "X_4") (pintype "bidirectional"))
      (node (ref "IC5") (pin "4") (pinfunction "IN+_4") (pintype "bidirectional"))
    )
    (net (code "30") (name "Net-(IC7A-A)") (class "Default")
      (node (ref "C17") (pin "2") (pinfunction "2_2") (pintype "passive"))
      (node (ref "C20") (pin "2") (pinfunction "2_2") (pintype "passive"))
      (node (ref "IC7") (pin "3") (pinfunction "A_3") (pintype "bidirectional"))
      (node (ref "IC8") (pin "3") (pinfunction "A_3") (pintype "bidirectional"))
      (node (ref "R11") (pin "1") (pinfunction "1_1") (pintype "passive"))
      (node (ref "R13") (pin "1") (pinfunction "1_1") (pintype "passive"))
    )
    (net (code "31") (name "Net-(IC7A-B)") (class "Default")
      (node (ref "IC7") (pin "1") (pinfunction "B_1") (pintype "bidirectional"))
      (node (ref "IC8") (pin "1") (pinfunction "B_1") (pintype "bidirectional"))
      (node (ref "R14") (pin "2") (pinfunction "2_2") (pintype "passive"))
    )
    (net (code "32") (name "Net-(IC7A-X)") (class "Default")
      (node (ref "C18") (pin "2") (pinfunction "2_2") (pintype "passive"))
      (node (ref "D4") (pin "A") (pinfunction "A_A") (pintype "passive"))
      (node (ref "IC7") (pin "4") (pinfunction "X_4") (pintype "bidirectional"))
      (node (ref "R12") (pin "2") (pinfunction "2_2") (pintype "passive"))
    )
    (net (code "33") (name "Net-(IC8A-X)") (class "Default")
      (node (ref "IC8") (pin "4") (pinfunction "X_4") (pintype "bidirectional"))
      (node (ref "IC9") (pin "5") (pinfunction "+IN_5") (pintype "input"))
    )
    (net (code "34") (name "Net-(IC9A-+IN)") (class "Default")
      (node (ref "IC9") (pin "3") (pinfunction "+IN_3") (pintype "input"))
      (node (ref "R19") (pin "2") (pinfunction "2_2") (pintype "passive"))
      (node (ref "R20") (pin "1") (pinfunction "1_1") (pintype "passive"))
    )
    (net (code "35") (name "Net-(LED1-VCC)") (class "Default")
      (node (ref "LED1") (pin "2") (pinfunction "VCC_2") (pintype "bidirectional"))
      (node (ref "R6") (pin "2") (pinfunction "2_2") (pintype "passive"))
    )
    (net (code "36") (name "Net-(P2-1)") (class "Default")
      (node (ref "C18") (pin "1") (pinfunction "1_1") (pintype "passive"))
      (node (ref "P2") (pin "P$1") (pinfunction "1_P$1") (pintype "passive"))
      (node (ref "R12") (pin "1") (pinfunction "1_1") (pintype "passive"))
    )
    (net (code "37") (name "Net-(Q2-B)") (class "Default")
      (node (ref "Q2") (pin "1") (pinfunction "B_1") (pintype "passive"))
      (node (ref "R7") (pin "2") (pinfunction "2_2") (pintype "passive"))
    )
    (net (code "38") (name "Net-(Q2-C)") (class "Default")
      (node (ref "Q2") (pin "3") (pinfunction "C_3") (pintype "passive"))
      (node (ref "SG1") (pin "-") (pinfunction "2_-") (pintype "passive"))
    )
    (net (code "39") (name "Net-(SG1-1)") (class "Default")
      (node (ref "R8") (pin "1") (pinfunction "1_1") (pintype "passive"))
      (node (ref "SG1") (pin "+") (pinfunction "1_+") (pintype "passive"))
    )
    (net (code "40") (name "Net-(U1-PF0)") (class "Default")
      (node (ref "C12") (pin "1") (pinfunction "1_1") (pintype "passive"))
      (node (ref "Q1") (pin "1") (pinfunction "1_1") (pintype "passive"))
      (node (ref "U1") (pin "5") (pinfunction "PF0_5") (pintype "bidirectional"))
    )
    (net (code "41") (name "Net-(U1-PF1)") (class "Default")
      (node (ref "C13") (pin "1") (pinfunction "1_1") (pintype "passive"))
      (node (ref "Q1") (pin "2") (pinfunction "2_2") (pintype "passive"))
      (node (ref "U1") (pin "6") (pinfunction "PF1_6") (pintype "bidirectional"))
    )
    (net (code "42") (name "Net-(U1-VDDA)") (class "Default")
      (node (ref "C4") (pin "1") (pinfunction "1_1") (pintype "passive"))
      (node (ref "C6") (pin "1") (pinfunction "1_1") (pintype "passive"))
      (node (ref "C7") (pin "1") (pinfunction "1_1") (pintype "passive"))
      (node (ref "C8") (pin "1") (pinfunction "1_1") (pintype "passive"))
      (node (ref "FB1") (pin "2") (pinfunction "2_2") (pintype "passive"))
      (node (ref "U1") (pin "24") (pinfunction "VDDSD_24") (pintype "bidirectional"))
      (node (ref "U1") (pin "9") (pinfunction "VDDA_9") (pintype "bidirectional"))
    )
    (net (code "43") (name "OFSEL") (class "Default")
      (node (ref "IC2") (pin "6") (pinfunction "~{A}/B_6") (pintype "input"))
      (node (ref "U1") (pin "33") (pinfunction "PA12_33") (pintype "bidirectional"))
    )
    (net (code "44") (name "RX") (class "Default")
      (node (ref "PWR") (pin "3") (pinfunction "3_3") (pintype "passive"))
      (node (ref "U1") (pin "31") (pinfunction "PA10_31") (pintype "bidirectional"))
    )
    (net (code "45") (name "SCL") (class "Default")
      (node (ref "EXP") (pin "3") (pinfunction "3_3") (pintype "passive"))
      (node (ref "R1") (pin "2") (pinfunction "2_2") (pintype "passive"))
      (node (ref "U1") (pin "45") (pinfunction "PB8_45") (pintype "bidirectional"))
      (node (ref "U2") (pin "6") (pinfunction "SCL_6") (pintype "bidirectional"))
    )
    (net (code "46") (name "SDA") (class "Default")
      (node (ref "EXP") (pin "2") (pinfunction "2_2") (pintype "passive"))
      (node (ref "R2") (pin "2") (pinfunction "2_2") (pintype "passive"))
      (node (ref "U1") (pin "46") (pinfunction "PB9_46") (pintype "bidirectional"))
      (node (ref "U2") (pin "5") (pinfunction "SDA_5") (pintype "bidirectional"))
    )
    (net (code "47") (name "SWCLK") (class "Default")
      (node (ref "EXP") (pin "6") (pinfunction "6_6") (pintype "passive"))
      (node (ref "U1") (pin "37") (pinfunction "PA14_37") (pintype "bidirectional"))
    )
    (net (code "48") (name "SWDIO") (class "Default")
      (node (ref "EXP") (pin "5") (pinfunction "5_5") (pintype "passive"))
      (node (ref "U1") (pin "34") (pinfunction "PA13_34") (pintype "bidirectional"))
    )
    (net (code "49") (name "TP1A") (class "Default")
      (node (ref "R21") (pin "2") (pinfunction "2_2") (pintype "passive"))
      (node (ref "R23") (pin "2") (pinfunction "2_2") (pintype "passive"))
      (node (ref "R25") (pin "1") (pinfunction "1_1") (pintype "passive"))
      (node (ref "TP") (pin "5") (pinfunction "5_5") (pintype "passive"))
      (node (ref "TP") (pin "6") (pinfunction "6_6") (pintype "passive"))
      (node (ref "TP") (pin "7") (pinfunction "7_7") (pintype "passive"))
      (node (ref "TP") (pin "8") (pinfunction "8_8") (pintype "passive"))
      (node (ref "TPCON") (pin "2") (pinfunction "2_2") (pintype "passive"))
      (node (ref "U1") (pin "12") (pinfunction "PA2_12") (pintype "bidirectional"))
    )
    (net (code "50") (name "TP1H") (class "Default")
      (node (ref "R25") (pin "2") (pinfunction "2_2") (pintype "passive"))
      (node (ref "U1") (pin "27") (pinfunction "PB15_27") (pintype "bidirectional"))
    )
    (net (code "51") (name "TP1L") (class "Default")
      (node (ref "R21") (pin "1") (pinfunction "1_1") (pintype "passive"))
      (node (ref "U1") (pin "26") (pinfunction "PB14_26") (pintype "bidirectional"))
    )
    (net (code "52") (name "TP1M") (class "Default")
      (node (ref "R23") (pin "1") (pinfunction "1_1") (pintype "passive"))
      (node (ref "U1") (pin "16") (pinfunction "PA6_16") (pintype "bidirectional"))
    )
    (net (code "53") (name "TP2A") (class "Default")
      (node (ref "P4") (pin "P$1") (pinfunction "1_P$1") (pintype "passive"))
      (node (ref "R22") (pin "2") (pinfunction "2_2") (pintype "passive"))
      (node (ref "R24") (pin "2") (pinfunction "2_2") (pintype "passive"))
      (node (ref "R26") (pin "1") (pinfunction "1_1") (pintype "passive"))
      (node (ref "TP") (pin "1") (pinfunction "1_1") (pintype "passive"))
      (node (ref "TP") (pin "2") (pinfunction "2_2") (pintype "passive"))
      (node (ref "TP") (pin "3") (pinfunction "3_3") (pintype "passive"))
      (node (ref "TP") (pin "4") (pinfunction "4_4") (pintype "passive"))
      (node (ref "TPCON") (pin "1") (pinfunction "1_1") (pintype "passive"))
      (node (ref "U1") (pin "11") (pinfunction "PA1_11") (pintype "bidirectional"))
    )
    (net (code "54") (name "TP2H") (class "Default")
      (node (ref "R26") (pin "2") (pinfunction "2_2") (pintype "passive"))
      (node (ref "U1") (pin "13") (pinfunction "PA3_13") (pintype "bidirectional"))
    )
    (net (code "55") (name "TP2L") (class "Default")
      (node (ref "R22") (pin "1") (pinfunction "1_1") (pintype "passive"))
      (node (ref "U1") (pin "15") (pinfunction "PA5_15") (pintype "bidirectional"))
    )
    (net (code "56") (name "TP2M") (class "Default")
      (node (ref "R24") (pin "1") (pinfunction "1_1") (pintype "passive"))
      (node (ref "U1") (pin "14") (pinfunction "PA4_14") (pintype "bidirectional"))
    )
    (net (code "57") (name "TX") (class "Default")
      (node (ref "PWR") (pin "2") (pinfunction "2_2") (pintype "passive"))
      (node (ref "U1") (pin "30") (pinfunction "PA9_30") (pintype "bidirectional"))
    )
    (net (code "58") (name "VREF") (class "Default")
      (node (ref "C22") (pin "1") (pinfunction "1_1") (pintype "passive"))
      (node (ref "IC6") (pin "7") (pinfunction "OUT_7") (pintype "bidirectional"))
      (node (ref "IC6") (pin "8") (pinfunction "FB_8") (pintype "bidirectional"))
      (node (ref "R19") (pin "1") (pinfunction "1_1") (pintype "passive"))
      (node (ref "U1") (pin "25") (pinfunction "VREFSD+_25") (pintype "bidirectional"))
    )
    (net (code "59") (name "VREF{slash}2") (class "Default")
      (node (ref "C24") (pin "1") (pinfunction "1_1") (pintype "passive"))
      (node (ref "IC2") (pin "3") (pinfunction "A_3") (pintype "bidirectional"))
      (node (ref "IC5") (pin "1") (pinfunction "REF_1") (pintype "bidirectional"))
      (node (ref "IC5") (pin "5") (pinfunction "IN-_5") (pintype "bidirectional"))
      (node (ref "IC9") (pin "1") (pinfunction "OUT_1") (pintype "output"))
      (node (ref "IC9") (pin "2") (pinfunction "-IN_2") (pintype "input"))
      (node (ref "U1") (pin "19") (pinfunction "PB1_19") (pintype "bidirectional"))
      (node (ref "U1") (pin "22") (pinfunction "PE9_22") (pintype "bidirectional"))
    )
    (net (code "60") (name "VSEL0") (class "Default")
      (node (ref "IC3") (pin "6") (pinfunction "~{A}/B_6") (pintype "input"))
      (node (ref "U1") (pin "35") (pinfunction "PF6_35") (pintype "bidirectional"))
    )
    (net (code "61") (name "VSEL1") (class "Default")
      (node (ref "IC7") (pin "6") (pinfunction "~{A}/B_6") (pintype "input"))
      (node (ref "IC8") (pin "6") (pinfunction "~{A}/B_6") (pintype "input"))
      (node (ref "U1") (pin "36") (pinfunction "PF7_36") (pintype "bidirectional"))
    )
    (net (code "62") (name "V_BATT") (class "Default")
      (node (ref "R4") (pin "1") (pinfunction "1_1") (pintype "passive"))
      (node (ref "SW1") (pin "P$1") (pinfunction "NC1_P$1") (pintype "passive"))
    )
    (net (code "63") (name "unconnected-(LED1-BLUE-Pad4)") (class "Default")
      (node (ref "LED1") (pin "4") (pinfunction "BLUE_4") (pintype "bidirectional"))
    )
    (net (code "64") (name "unconnected-(SW1-NO1-PadP$3)") (class "Default")
      (node (ref "SW1") (pin "P$3") (pinfunction "NO1_P$3") (pintype "passive"))
    )
    (net (code "65") (name "unconnected-(SW1-NO2-PadP$4)") (class "Default")
      (node (ref "SW1") (pin "P$4") (pinfunction "NO2_P$4") (pintype "passive"))
    )
    (net (code "66") (name "unconnected-(U1-PD8-Pad28)") (class "Default")
      (node (ref "U1") (pin "28") (pinfunction "PD8_28") (pintype "bidirectional"))
    )
  )
)
